# ProPrj___2024-09-22.net
KiCad netlist of a schematic drawn in EasyEDA Pro
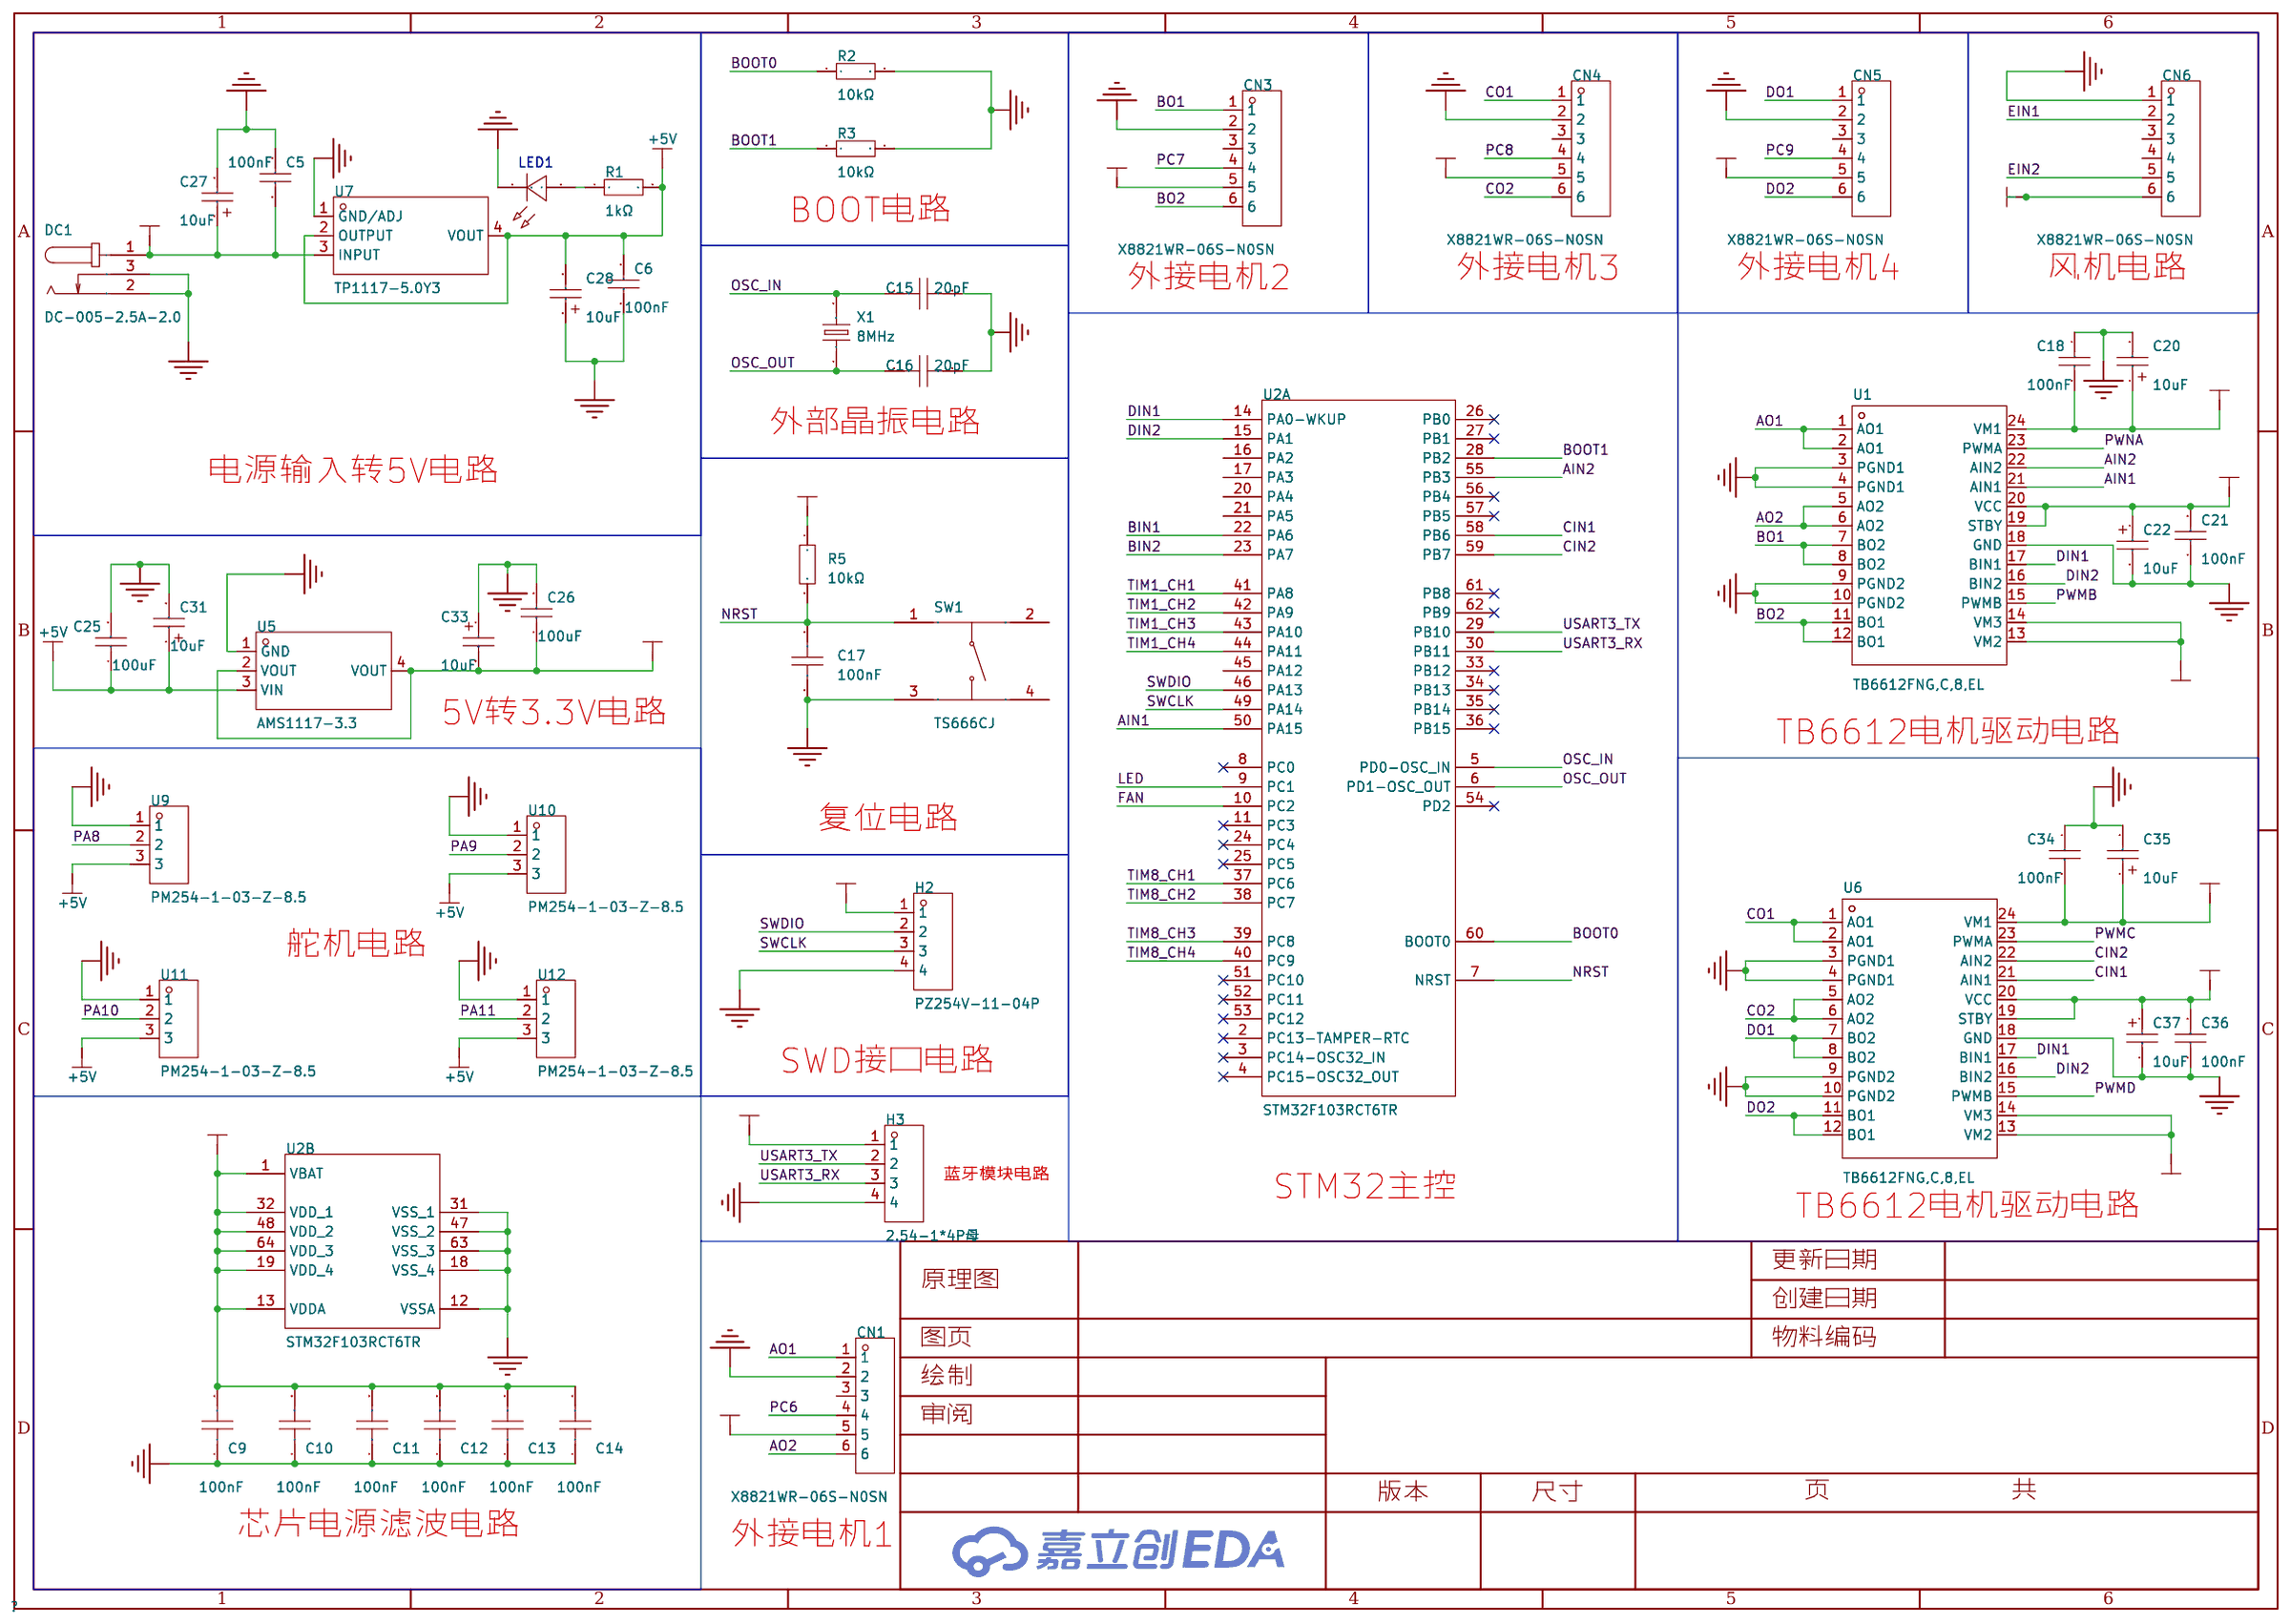
[diagram p0: schematic sheet]

(export (version "E")
  (design (tool "Eeschema 10.0.6"))
  (components
    (comp (ref "C5")
      (value "100nF")
      (footprint "easyedapro:C0805")
      (description "容值:100nF;精度:±10%;额定电压:50V;材质(温度系数):X7R;")
      (fields
        (field (name "Manufacturer Part") "CC0805KRX7R9BB104")
        (field (name "Manufacturer") "YAGEO(国巨)")
      )
      (libsource (lib "easyedapro") (part "CC0805KRX7R9BB104"))
    )
    (comp (ref "C6")
      (value "100nF")
      (footprint "easyedapro:C0805")
      (description "容值:100nF;精度:±10%;额定电压:50V;材质(温度系数):X7R;")
      (fields
        (field (name "Manufacturer Part") "CC0805KRX7R9BB104")
        (field (name "Manufacturer") "YAGEO(国巨)")
      )
      (libsource (lib "easyedapro") (part "CC0805KRX7R9BB104"))
    )
    (comp (ref "C9")
      (value "100nF")
      (footprint "easyedapro:C0603")
      (description "容值:100nF;精度:±10%;额定电压:50V;材质(温度系数):X7R;")
      (fields
        (field (name "Manufacturer Part") "CC0603KRX7R9BB104")
        (field (name "Manufacturer") "YAGEO(国巨)")
      )
      (libsource (lib "easyedapro") (part "CC0603KRX7R9BB104"))
    )
    (comp (ref "C10")
      (value "100nF")
      (footprint "easyedapro:C0603")
      (description "容值:100nF;精度:±10%;额定电压:50V;材质(温度系数):X7R;")
      (fields
        (field (name "Manufacturer Part") "CC0603KRX7R9BB104")
        (field (name "Manufacturer") "YAGEO(国巨)")
      )
      (libsource (lib "easyedapro") (part "CC0603KRX7R9BB104"))
    )
    (comp (ref "C11")
      (value "100nF")
      (footprint "easyedapro:C0603")
      (description "容值:100nF;精度:±10%;额定电压:50V;材质(温度系数):X7R;")
      (fields
        (field (name "Manufacturer Part") "CC0603KRX7R9BB104")
        (field (name "Manufacturer") "YAGEO(国巨)")
      )
      (libsource (lib "easyedapro") (part "CC0603KRX7R9BB104"))
    )
    (comp (ref "C12")
      (value "100nF")
      (footprint "easyedapro:C0603")
      (description "容值:100nF;精度:±10%;额定电压:50V;材质(温度系数):X7R;")
      (fields
        (field (name "Manufacturer Part") "CC0603KRX7R9BB104")
        (field (name "Manufacturer") "YAGEO(国巨)")
      )
      (libsource (lib "easyedapro") (part "CC0603KRX7R9BB104"))
    )
    (comp (ref "C13")
      (value "100nF")
      (footprint "easyedapro:C0603")
      (description "容值:100nF;精度:±10%;额定电压:50V;材质(温度系数):X7R;")
      (fields
        (field (name "Manufacturer Part") "CC0603KRX7R9BB104")
        (field (name "Manufacturer") "YAGEO(国巨)")
      )
      (libsource (lib "easyedapro") (part "CC0603KRX7R9BB104"))
    )
    (comp (ref "C14")
      (value "100nF")
      (footprint "easyedapro:C0603")
      (description "容值:100nF;精度:±10%;额定电压:50V;材质(温度系数):X7R;")
      (fields
        (field (name "Manufacturer Part") "CC0603KRX7R9BB104")
        (field (name "Manufacturer") "YAGEO(国巨)")
      )
      (libsource (lib "easyedapro") (part "CC0603KRX7R9BB104"))
    )
    (comp (ref "C15")
      (value "20pF")
      (footprint "easyedapro:C0805")
      (description "容值:20pF;精度:±5%;额定电压:50V;材质(温度系数):C0G;")
      (fields (field (name "Manufacturer Part") "0805CG200J500NT") (field (name "Manufacturer") "FH(风华)"))
      (libsource (lib "easyedapro") (part "0805CG200J500NT"))
    )
    (comp (ref "C16")
      (value "20pF")
      (footprint "easyedapro:C0805")
      (description "容值:20pF;精度:±5%;额定电压:50V;材质(温度系数):C0G;")
      (fields (field (name "Manufacturer Part") "0805CG200J500NT") (field (name "Manufacturer") "FH(风华)"))
      (libsource (lib "easyedapro") (part "0805CG200J500NT"))
    )
    (comp (ref "C17")
      (value "100nF")
      (footprint "easyedapro:C0603")
      (description "容值:100nF;精度:±10%;额定电压:50V;材质(温度系数):X7R;")
      (fields
        (field (name "Manufacturer Part") "CC0603KRX7R9BB104")
        (field (name "Manufacturer") "YAGEO(国巨)")
      )
      (libsource (lib "easyedapro") (part "CC0603KRX7R9BB104"))
    )
    (comp (ref "C18")
      (value "100nF")
      (footprint "easyedapro:C0805")
      (description "容值:100nF;精度:±10%;额定电压:50V;材质(温度系数):X7R;")
      (fields
        (field (name "Manufacturer Part") "CC0805KRX7R9BB104")
        (field (name "Manufacturer") "YAGEO(国巨)")
      )
      (libsource (lib "easyedapro") (part "CC0805KRX7R9BB104"))
    )
    (comp (ref "C20")
      (value "10uF")
      (footprint "easyedapro:CAP-SMD_L3.2-W1.6-RD-C7171")
      (description "容值:10uF;精度:±10%;额定电压:16V;等效串联电阻:3Ω@100kHz;")
      (fields (field (name "Manufacturer Part") "TAJA106K016RNJ") (field (name "Manufacturer") "Kyocera AVX"))
      (libsource (lib "easyedapro") (part "TAJA106K016RNJ"))
    )
    (comp (ref "C21")
      (value "100nF")
      (footprint "easyedapro:C0805")
      (description "容值:100nF;精度:±10%;额定电压:50V;材质(温度系数):X7R;")
      (fields
        (field (name "Manufacturer Part") "CC0805KRX7R9BB104")
        (field (name "Manufacturer") "YAGEO(国巨)")
      )
      (libsource (lib "easyedapro") (part "CC0805KRX7R9BB104"))
    )
    (comp (ref "C22")
      (value "10uF")
      (footprint "easyedapro:CAP-SMD_L3.2-W1.6-RD-C7171")
      (description "容值:10uF;精度:±10%;额定电压:16V;等效串联电阻:3Ω@100kHz;")
      (fields (field (name "Manufacturer Part") "TAJA106K016RNJ") (field (name "Manufacturer") "Kyocera AVX"))
      (libsource (lib "easyedapro") (part "TAJA106K016RNJ"))
    )
    (comp (ref "C25")
      (value "100uF")
      (footprint "easyedapro:C0805")
      (description "容值:100uF;精度:±20%;额定电压:6.3V;材质(温度系数):X5R;")
      (fields
        (field (name "Manufacturer Part") "GRM21BR60J107ME15L")
        (field (name "Manufacturer") "muRata(村田)")
      )
      (libsource (lib "easyedapro") (part "GRM21BR60J107ME15L"))
    )
    (comp (ref "C26")
      (value "100uF")
      (footprint "easyedapro:C0805")
      (description "容值:100uF;精度:±20%;额定电压:6.3V;材质(温度系数):X5R;")
      (fields
        (field (name "Manufacturer Part") "GRM21BR60J107ME15L")
        (field (name "Manufacturer") "muRata(村田)")
      )
      (libsource (lib "easyedapro") (part "GRM21BR60J107ME15L"))
    )
    (comp (ref "C27")
      (value "10uF")
      (footprint "easyedapro:CAP-SMD_L3.2-W1.6-RD-C7171")
      (description "容值:10uF;精度:±10%;额定电压:16V;等效串联电阻:3Ω@100kHz;")
      (fields (field (name "Manufacturer Part") "TAJA106K016RNJ") (field (name "Manufacturer") "Kyocera AVX"))
      (libsource (lib "easyedapro") (part "TAJA106K016RNJ"))
    )
    (comp (ref "C28")
      (value "10uF")
      (footprint "easyedapro:CAP-SMD_L3.2-W1.6-RD-C7171")
      (description "容值:10uF;精度:±10%;额定电压:16V;等效串联电阻:3Ω@100kHz;")
      (fields (field (name "Manufacturer Part") "TAJA106K016RNJ") (field (name "Manufacturer") "Kyocera AVX"))
      (libsource (lib "easyedapro") (part "TAJA106K016RNJ"))
    )
    (comp (ref "C31")
      (value "10uF")
      (footprint "easyedapro:CAP-SMD_L3.2-W1.6-RD-C7171")
      (description "容值:10uF;精度:±10%;额定电压:16V;等效串联电阻:3Ω@100kHz;")
      (fields (field (name "Manufacturer Part") "TAJA106K016RNJ") (field (name "Manufacturer") "Kyocera AVX"))
      (libsource (lib "easyedapro") (part "TAJA106K016RNJ"))
    )
    (comp (ref "C33")
      (value "10uF")
      (footprint "easyedapro:CAP-SMD_L3.2-W1.6-RD-C7171")
      (description "容值:10uF;精度:±10%;额定电压:16V;等效串联电阻:3Ω@100kHz;")
      (fields (field (name "Manufacturer Part") "TAJA106K016RNJ") (field (name "Manufacturer") "Kyocera AVX"))
      (libsource (lib "easyedapro") (part "TAJA106K016RNJ"))
    )
    (comp (ref "C34")
      (value "100nF")
      (footprint "easyedapro:C0805")
      (description "容值:100nF;精度:±10%;额定电压:50V;材质(温度系数):X7R;")
      (fields
        (field (name "Manufacturer Part") "CC0805KRX7R9BB104")
        (field (name "Manufacturer") "YAGEO(国巨)")
      )
      (libsource (lib "easyedapro") (part "CC0805KRX7R9BB104"))
    )
    (comp (ref "C35")
      (value "10uF")
      (footprint "easyedapro:CAP-SMD_L3.2-W1.6-RD-C7171")
      (description "容值:10uF;精度:±10%;额定电压:16V;等效串联电阻:3Ω@100kHz;")
      (fields (field (name "Manufacturer Part") "TAJA106K016RNJ") (field (name "Manufacturer") "Kyocera AVX"))
      (libsource (lib "easyedapro") (part "TAJA106K016RNJ"))
    )
    (comp (ref "C36")
      (value "100nF")
      (footprint "easyedapro:C0805")
      (description "容值:100nF;精度:±10%;额定电压:50V;材质(温度系数):X7R;")
      (fields
        (field (name "Manufacturer Part") "CC0805KRX7R9BB104")
        (field (name "Manufacturer") "YAGEO(国巨)")
      )
      (libsource (lib "easyedapro") (part "CC0805KRX7R9BB104"))
    )
    (comp (ref "C37")
      (value "10uF")
      (footprint "easyedapro:CAP-SMD_L3.2-W1.6-RD-C7171")
      (description "容值:10uF;精度:±10%;额定电压:16V;等效串联电阻:3Ω@100kHz;")
      (fields (field (name "Manufacturer Part") "TAJA106K016RNJ") (field (name "Manufacturer") "Kyocera AVX"))
      (libsource (lib "easyedapro") (part "TAJA106K016RNJ"))
    )
    (comp (ref "CN1")
      (value "X8821WR-06S-N0SN")
      (footprint "easyedapro:CONN-TH_6P-P2.50_X8821WR-06S-N2SN")
      (description "插针结构:1x6P;间距:2.5mm;安装方式:弯插;参考系列:XH;总PIN数:6P;排数:1;每排PIN数:6;行距:-;额定电流:3A;触头材质:黄铜;触头镀层:锡;工作温度范围:-;")
      (fields (field (name "Manufacturer") "XKB Connection(中国星坤)"))
      (libsource (lib "easyedapro") (part "X8821WR-06S-N0SN"))
    )
    (comp (ref "CN3")
      (value "X8821WR-06S-N0SN")
      (footprint "easyedapro:CONN-TH_6P-P2.50_X8821WR-06S-N2SN")
      (description "插针结构:1x6P;间距:2.5mm;安装方式:弯插;参考系列:XH;总PIN数:6P;排数:1;每排PIN数:6;行距:-;额定电流:3A;触头材质:黄铜;触头镀层:锡;工作温度范围:-;")
      (fields (field (name "Manufacturer") "XKB Connection(中国星坤)"))
      (libsource (lib "easyedapro") (part "X8821WR-06S-N0SN"))
    )
    (comp (ref "CN4")
      (value "X8821WR-06S-N0SN")
      (footprint "easyedapro:CONN-TH_6P-P2.50_X8821WR-06S-N2SN")
      (description "插针结构:1x6P;间距:2.5mm;安装方式:弯插;参考系列:XH;总PIN数:6P;排数:1;每排PIN数:6;行距:-;额定电流:3A;触头材质:黄铜;触头镀层:锡;工作温度范围:-;")
      (fields (field (name "Manufacturer") "XKB Connection(中国星坤)"))
      (libsource (lib "easyedapro") (part "X8821WR-06S-N0SN"))
    )
    (comp (ref "CN5")
      (value "X8821WR-06S-N0SN")
      (footprint "easyedapro:CONN-TH_6P-P2.50_X8821WR-06S-N2SN")
      (description "插针结构:1x6P;间距:2.5mm;安装方式:弯插;参考系列:XH;总PIN数:6P;排数:1;每排PIN数:6;行距:-;额定电流:3A;触头材质:黄铜;触头镀层:锡;工作温度范围:-;")
      (fields (field (name "Manufacturer") "XKB Connection(中国星坤)"))
      (libsource (lib "easyedapro") (part "X8821WR-06S-N0SN"))
    )
    (comp (ref "CN6")
      (value "X8821WR-06S-N0SN")
      (footprint "easyedapro:CONN-TH_6P-P2.50_X8821WR-06S-N2SN")
      (description "插针结构:1x6P;间距:2.5mm;安装方式:弯插;参考系列:XH;总PIN数:6P;排数:1;每排PIN数:6;行距:-;额定电流:3A;触头材质:黄铜;触头镀层:锡;工作温度范围:-;")
      (fields (field (name "Manufacturer") "XKB Connection(中国星坤)"))
      (libsource (lib "easyedapro") (part "X8821WR-06S-N0SN"))
    )
    (comp (ref "DC1")
      (value "DC-005-2.5A-2.0")
      (footprint "easyedapro:CONN-TH_DC-005-2.5A-2.0")
      (fields (field (name "Manufacturer") "XKB Connection(中国星坤)"))
      (libsource (lib "easyedapro") (part "DC-005-2.5A-2.0"))
    )
    (comp (ref "H2")
      (value "PZ254V-11-04P")
      (footprint "easyedapro:HDR-TH_4P-P2.54-V-M")
      (fields (field (name "Manufacturer") "XFCN(兴飞)"))
      (libsource (lib "easyedapro") (part "PZ254V-11-04P_C2691448"))
    )
    (comp (ref "H3")
      (value "2.54-1*4P母")
      (footprint "easyedapro:HDR-TH_4P-P2.54-V-F")
      (fields (field (name "Manufacturer") "BOOMELE(博穆精密)"))
      (libsource (lib "easyedapro") (part "2.54-1*4P母"))
    )
    (comp (ref "LED1")
      (value "~")
      (footprint "easyedapro:LED_0805")
      (libsource (lib "easyedapro") (part "LED_B"))
    )
    (comp (ref "R1")
      (value "1kΩ")
      (footprint "easyedapro:R0805")
      (description "电阻类型:厚膜电阻;阻值:1kΩ;精度:±1%;功率:125mW;最大工作电压:150V;温度系数:±100ppm/°C;")
      (fields
        (field (name "Manufacturer Part") "0805W8F1001T5E")
        (field (name "Manufacturer") "UNI-ROYAL(厚声)")
      )
      (libsource (lib "easyedapro") (part "0805W8F1001T5E"))
    )
    (comp (ref "R2")
      (value "10kΩ")
      (footprint "easyedapro:R0603")
      (description "电阻类型:厚膜电阻;阻值:10kΩ;精度:±1%;功率:100mW;最大工作电压:75V;温度系数:±100ppm/°C;")
      (fields
        (field (name "Manufacturer Part") "0603WAF1002T5E")
        (field (name "Manufacturer") "UNI-ROYAL(厚声)")
      )
      (libsource (lib "easyedapro") (part "0603WAF1002T5E"))
    )
    (comp (ref "R3")
      (value "10kΩ")
      (footprint "easyedapro:R0603")
      (description "电阻类型:厚膜电阻;阻值:10kΩ;精度:±1%;功率:100mW;最大工作电压:75V;温度系数:±100ppm/°C;")
      (fields
        (field (name "Manufacturer Part") "0603WAF1002T5E")
        (field (name "Manufacturer") "UNI-ROYAL(厚声)")
      )
      (libsource (lib "easyedapro") (part "0603WAF1002T5E"))
    )
    (comp (ref "R5")
      (value "10kΩ")
      (footprint "easyedapro:R0603")
      (description "电阻类型:厚膜电阻;阻值:10kΩ;精度:±1%;功率:100mW;最大工作电压:75V;温度系数:±100ppm/°C;")
      (fields
        (field (name "Manufacturer Part") "0603WAF1002T5E")
        (field (name "Manufacturer") "UNI-ROYAL(厚声)")
      )
      (libsource (lib "easyedapro") (part "0603WAF1002T5E"))
    )
    (comp (ref "SW1")
      (value "TS666CJ")
      (footprint "easyedapro:SW-TH_4P-L6.0-W6.0-P4.50-LS6.5")
      (fields (field (name "Manufacturer") "SHOU HAN(首韩)"))
      (libsource (lib "easyedapro") (part "TS666CJ"))
    )
    (comp (ref "U1")
      (value "TB6612FNG,C,8,EL")
      (footprint "easyedapro:SSOP-24_L8.3-W5.6-P0.65-LS7.6-BL")
      (fields (field (name "Manufacturer") "TOSHIBA(东芝)"))
      (libsource (lib "easyedapro") (part "TB6612FNG,C,8,EL"))
    )
    (comp (ref "U2")
      (value "STM32F103RCT6TR")
      (footprint "easyedapro:LQFP-64_L10.0-W10.0-P0.50-LS12.0-BL")
      (description "CPU内核:ARM-M3;程序存储容量:256KB;RAM总容量:48KB;GPIO端口数量:51;工作电压范围:2V~3.6V;CPU最大主频:72MHz;程序存储器类型:FLASH;")
      (fields (field (name "Manufacturer") "ST(意法半导体)"))
      (libsource (lib "easyedapro") (part "STM32F103RCT6TR"))
    )
    (comp (ref "U5")
      (value "AMS1117-3.3")
      (footprint "easyedapro:SOT-223-3_L6.5-W3.4-P2.30-LS7.0-BR")
      (description "输出类型:固定;最大输入电压:-;输出电压:3.3V;最大输出电流:1A;电源纹波抑制比(PSRR):72dB@(120Hz);输出极性:正极;")
      (fields (field (name "Manufacturer") "AMS"))
      (libsource (lib "easyedapro") (part "AMS1117-3.3"))
    )
    (comp (ref "U6")
      (value "TB6612FNG,C,8,EL")
      (footprint "easyedapro:SSOP-24_L8.3-W5.6-P0.65-LS7.6-BL")
      (fields (field (name "Manufacturer") "TOSHIBA(东芝)"))
      (libsource (lib "easyedapro") (part "TB6612FNG,C,8,EL"))
    )
    (comp (ref "U7")
      (value "TP1117-5.0Y3")
      (footprint "easyedapro:SOT-223-3_L6.5-W3.4-P2.30-LS7.0-BR")
      (fields (field (name "Manufacturer") "TECH PUBLIC(台舟)"))
      (libsource (lib "easyedapro") (part "TP1117-5.0Y3"))
    )
    (comp (ref "U9")
      (value "PM254-1-03-Z-8.5")
      (footprint "easyedapro:HDR-TH_3P-P2.54-V-F")
      (fields (field (name "Manufacturer") "HCTL(华灿天禄)"))
      (libsource (lib "easyedapro") (part "PM254-1-03-Z-8.5"))
    )
    (comp (ref "U10")
      (value "PM254-1-03-Z-8.5")
      (footprint "easyedapro:HDR-TH_3P-P2.54-V-F")
      (fields (field (name "Manufacturer") "HCTL(华灿天禄)"))
      (libsource (lib "easyedapro") (part "PM254-1-03-Z-8.5"))
    )
    (comp (ref "U11")
      (value "PM254-1-03-Z-8.5")
      (footprint "easyedapro:HDR-TH_3P-P2.54-V-F")
      (fields (field (name "Manufacturer") "HCTL(华灿天禄)"))
      (libsource (lib "easyedapro") (part "PM254-1-03-Z-8.5"))
    )
    (comp (ref "U12")
      (value "PM254-1-03-Z-8.5")
      (footprint "easyedapro:HDR-TH_3P-P2.54-V-F")
      (fields (field (name "Manufacturer") "HCTL(华灿天禄)"))
      (libsource (lib "easyedapro") (part "PM254-1-03-Z-8.5"))
    )
    (comp (ref "X1")
      (value "8MHz")
      (footprint "easyedapro:HC-49US_L11.5-W4.5-P4.88")
      (description "晶振类型:直插晶振;频率:8MHz;常温频差:±20ppm;外接负载电容:20pF;频率稳定度(全温):±20ppm;")
      (fields
        (field (name "Manufacturer Part") "49S-8.000-20-20-20/A")
        (field (name "Manufacturer") "LIMING(利明)")
      )
      (libsource (lib "easyedapro") (part "49S-8.000-20-20-20/A"))
    )
  )
  (nets
    (net (code "1") (name "+3.3V") (class "Default")
      (node (ref "C10") (pin "2") (pinfunction "2_2") (pintype "unspecified"))
      (node (ref "C11") (pin "2") (pinfunction "2_2") (pintype "unspecified"))
      (node (ref "C12") (pin "2") (pinfunction "2_2") (pintype "unspecified"))
      (node (ref "C13") (pin "2") (pinfunction "2_2") (pintype "unspecified"))
      (node (ref "C14") (pin "2") (pinfunction "2_2") (pintype "unspecified"))
      (node (ref "C21") (pin "2") (pinfunction "2_2") (pintype "input"))
      (node (ref "C22") (pin "1") (pinfunction "1_1") (pintype "input"))
      (node (ref "C26") (pin "1") (pinfunction "1_1") (pintype "input"))
      (node (ref "C33") (pin "2") (pinfunction "2_2") (pintype "input"))
      (node (ref "C36") (pin "2") (pinfunction "2_2") (pintype "input"))
      (node (ref "C37") (pin "1") (pinfunction "1_1") (pintype "input"))
      (node (ref "C9") (pin "2") (pinfunction "2_2") (pintype "unspecified"))
      (node (ref "CN1") (pin "5") (pinfunction "5_5") (pintype "unspecified"))
      (node (ref "CN3") (pin "5") (pinfunction "5_5") (pintype "unspecified"))
      (node (ref "CN4") (pin "5") (pinfunction "5_5") (pintype "unspecified"))
      (node (ref "CN5") (pin "5") (pinfunction "5_5") (pintype "unspecified"))
      (node (ref "H2") (pin "1") (pinfunction "1_1") (pintype "unspecified"))
      (node (ref "H3") (pin "1") (pinfunction "1_1") (pintype "unspecified"))
      (node (ref "R5") (pin "1") (pinfunction "1_1") (pintype "input"))
      (node (ref "U1") (pin "19") (pinfunction "STBY_19") (pintype "unspecified"))
      (node (ref "U1") (pin "20") (pinfunction "VCC_20") (pintype "unspecified"))
      (node (ref "U2") (pin "1") (pinfunction "VBAT_1") (pintype "unspecified"))
      (node (ref "U2") (pin "13") (pinfunction "VDDA_13") (pintype "unspecified"))
      (node (ref "U2") (pin "19") (pinfunction "VDD_4_19") (pintype "unspecified"))
      (node (ref "U2") (pin "32") (pinfunction "VDD_1_32") (pintype "unspecified"))
      (node (ref "U2") (pin "48") (pinfunction "VDD_2_48") (pintype "unspecified"))
      (node (ref "U2") (pin "64") (pinfunction "VDD_3_64") (pintype "unspecified"))
      (node (ref "U5") (pin "2") (pinfunction "VOUT_2") (pintype "unspecified"))
      (node (ref "U5") (pin "4") (pinfunction "VOUT_4") (pintype "unspecified"))
      (node (ref "U6") (pin "19") (pinfunction "STBY_19") (pintype "unspecified"))
      (node (ref "U6") (pin "20") (pinfunction "VCC_20") (pintype "unspecified"))
    )
    (net (code "2") (name "+5V") (class "Default")
      (node (ref "C25") (pin "1") (pinfunction "1_1") (pintype "input"))
      (node (ref "C28") (pin "2") (pinfunction "2_2") (pintype "input"))
      (node (ref "C31") (pin "1") (pinfunction "1_1") (pintype "input"))
      (node (ref "C6") (pin "1") (pinfunction "1_1") (pintype "input"))
      (node (ref "R1") (pin "2") (pinfunction "2_2") (pintype "input"))
      (node (ref "U10") (pin "3") (pinfunction "3_3") (pintype "unspecified"))
      (node (ref "U11") (pin "3") (pinfunction "3_3") (pintype "unspecified"))
      (node (ref "U12") (pin "3") (pinfunction "3_3") (pintype "unspecified"))
      (node (ref "U5") (pin "3") (pinfunction "VIN_3") (pintype "unspecified"))
      (node (ref "U7") (pin "2") (pinfunction "OUTPUT_2") (pintype "unspecified"))
      (node (ref "U7") (pin "4") (pinfunction "VOUT_4") (pintype "unspecified"))
      (node (ref "U9") (pin "3") (pinfunction "3_3") (pintype "unspecified"))
    )
    (net (code "3") (name "+8V") (class "Default")
      (node (ref "C18") (pin "2") (pinfunction "2_2") (pintype "input"))
      (node (ref "C20") (pin "1") (pinfunction "1_1") (pintype "input"))
      (node (ref "C34") (pin "2") (pinfunction "2_2") (pintype "input"))
      (node (ref "C35") (pin "1") (pinfunction "1_1") (pintype "input"))
      (node (ref "U1") (pin "13") (pinfunction "VM2_13") (pintype "unspecified"))
      (node (ref "U1") (pin "14") (pinfunction "VM3_14") (pintype "unspecified"))
      (node (ref "U1") (pin "24") (pinfunction "VM1_24") (pintype "unspecified"))
      (node (ref "U6") (pin "13") (pinfunction "VM2_13") (pintype "unspecified"))
      (node (ref "U6") (pin "14") (pinfunction "VM3_14") (pintype "unspecified"))
      (node (ref "U6") (pin "24") (pinfunction "VM1_24") (pintype "unspecified"))
    )
    (net (code "4") (name "+12V") (class "Default")
      (node (ref "CN6") (pin "6") (pinfunction "6_6") (pintype "unspecified"))
    )
    (net (code "5") (name "/AIN1") (class "Default")
      (node (ref "U1") (pin "21") (pinfunction "AIN1_21") (pintype "unspecified"))
      (node (ref "U2") (pin "50") (pinfunction "PA15_50") (pintype "bidirectional"))
    )
    (net (code "6") (name "/AIN2") (class "Default")
      (node (ref "U1") (pin "22") (pinfunction "AIN2_22") (pintype "unspecified"))
      (node (ref "U2") (pin "55") (pinfunction "PB3_55") (pintype "bidirectional"))
    )
    (net (code "7") (name "/AO1") (class "Default")
      (node (ref "CN1") (pin "1") (pinfunction "1_1") (pintype "unspecified"))
      (node (ref "U1") (pin "1") (pinfunction "AO1_1") (pintype "unspecified"))
      (node (ref "U1") (pin "2") (pinfunction "AO1_2") (pintype "unspecified"))
    )
    (net (code "8") (name "/AO2") (class "Default")
      (node (ref "CN1") (pin "6") (pinfunction "6_6") (pintype "unspecified"))
      (node (ref "U1") (pin "5") (pinfunction "AO2_5") (pintype "unspecified"))
      (node (ref "U1") (pin "6") (pinfunction "AO2_6") (pintype "unspecified"))
    )
    (net (code "9") (name "/BIN1") (class "Default")
      (node (ref "U2") (pin "22") (pinfunction "PA6_22") (pintype "bidirectional"))
    )
    (net (code "10") (name "/BIN2") (class "Default")
      (node (ref "U2") (pin "23") (pinfunction "PA7_23") (pintype "bidirectional"))
    )
    (net (code "11") (name "/BO1") (class "Default")
      (node (ref "CN3") (pin "1") (pinfunction "1_1") (pintype "unspecified"))
      (node (ref "U1") (pin "7") (pinfunction "BO2_7") (pintype "unspecified"))
      (node (ref "U1") (pin "8") (pinfunction "BO2_8") (pintype "unspecified"))
    )
    (net (code "12") (name "/BO2") (class "Default")
      (node (ref "CN3") (pin "6") (pinfunction "6_6") (pintype "unspecified"))
      (node (ref "U1") (pin "11") (pinfunction "BO1_11") (pintype "unspecified"))
      (node (ref "U1") (pin "12") (pinfunction "BO1_12") (pintype "unspecified"))
    )
    (net (code "13") (name "/BOOT0") (class "Default")
      (node (ref "R2") (pin "1") (pinfunction "1_1") (pintype "input"))
      (node (ref "U2") (pin "60") (pinfunction "BOOT0_60") (pintype "unspecified"))
    )
    (net (code "14") (name "/BOOT1") (class "Default")
      (node (ref "R3") (pin "1") (pinfunction "1_1") (pintype "input"))
      (node (ref "U2") (pin "28") (pinfunction "PB2_28") (pintype "bidirectional"))
    )
    (net (code "15") (name "/CIN1") (class "Default")
      (node (ref "U2") (pin "58") (pinfunction "PB6_58") (pintype "bidirectional"))
      (node (ref "U6") (pin "21") (pinfunction "AIN1_21") (pintype "unspecified"))
    )
    (net (code "16") (name "/CIN2") (class "Default")
      (node (ref "U2") (pin "59") (pinfunction "PB7_59") (pintype "bidirectional"))
      (node (ref "U6") (pin "22") (pinfunction "AIN2_22") (pintype "unspecified"))
    )
    (net (code "17") (name "/CO1") (class "Default")
      (node (ref "CN4") (pin "1") (pinfunction "1_1") (pintype "unspecified"))
      (node (ref "U6") (pin "1") (pinfunction "AO1_1") (pintype "unspecified"))
      (node (ref "U6") (pin "2") (pinfunction "AO1_2") (pintype "unspecified"))
    )
    (net (code "18") (name "/CO2") (class "Default")
      (node (ref "CN4") (pin "6") (pinfunction "6_6") (pintype "unspecified"))
      (node (ref "U6") (pin "5") (pinfunction "AO2_5") (pintype "unspecified"))
      (node (ref "U6") (pin "6") (pinfunction "AO2_6") (pintype "unspecified"))
    )
    (net (code "19") (name "/DIN1") (class "Default")
      (node (ref "U1") (pin "17") (pinfunction "BIN1_17") (pintype "unspecified"))
      (node (ref "U2") (pin "14") (pinfunction "PA0-WKUP_14") (pintype "bidirectional"))
      (node (ref "U6") (pin "17") (pinfunction "BIN1_17") (pintype "unspecified"))
    )
    (net (code "20") (name "/DIN2") (class "Default")
      (node (ref "U1") (pin "16") (pinfunction "BIN2_16") (pintype "unspecified"))
      (node (ref "U2") (pin "15") (pinfunction "PA1_15") (pintype "bidirectional"))
      (node (ref "U6") (pin "16") (pinfunction "BIN2_16") (pintype "unspecified"))
    )
    (net (code "21") (name "/DO1") (class "Default")
      (node (ref "CN5") (pin "1") (pinfunction "1_1") (pintype "unspecified"))
      (node (ref "U6") (pin "7") (pinfunction "BO2_7") (pintype "unspecified"))
      (node (ref "U6") (pin "8") (pinfunction "BO2_8") (pintype "unspecified"))
    )
    (net (code "22") (name "/DO2") (class "Default")
      (node (ref "CN5") (pin "6") (pinfunction "6_6") (pintype "unspecified"))
      (node (ref "U6") (pin "11") (pinfunction "BO1_11") (pintype "unspecified"))
      (node (ref "U6") (pin "12") (pinfunction "BO1_12") (pintype "unspecified"))
    )
    (net (code "23") (name "/EIN1") (class "Default")
      (node (ref "CN6") (pin "2") (pinfunction "2_2") (pintype "unspecified"))
    )
    (net (code "24") (name "/EIN2") (class "Default")
      (node (ref "CN6") (pin "5") (pinfunction "5_5") (pintype "unspecified"))
    )
    (net (code "25") (name "/FAN") (class "Default")
      (node (ref "U2") (pin "10") (pinfunction "PC2_10") (pintype "bidirectional"))
    )
    (net (code "26") (name "/LED") (class "Default")
      (node (ref "U2") (pin "9") (pinfunction "PC1_9") (pintype "bidirectional"))
    )
    (net (code "27") (name "/NRST") (class "Default")
      (node (ref "C17") (pin "2") (pinfunction "2_2") (pintype "unspecified"))
      (node (ref "R5") (pin "2") (pinfunction "2_2") (pintype "input"))
      (node (ref "SW1") (pin "1") (pinfunction "A_1") (pintype "input"))
      (node (ref "U2") (pin "7") (pinfunction "NRST_7") (pintype "bidirectional"))
    )
    (net (code "28") (name "/OSC_IN") (class "Default")
      (node (ref "C15") (pin "1") (pinfunction "1_1") (pintype "unspecified"))
      (node (ref "U2") (pin "5") (pinfunction "PD0-OSC_IN_5") (pintype "bidirectional"))
      (node (ref "X1") (pin "2") (pinfunction "2_2") (pintype "input"))
    )
    (net (code "29") (name "/OSC_OUT") (class "Default")
      (node (ref "C16") (pin "1") (pinfunction "1_1") (pintype "unspecified"))
      (node (ref "U2") (pin "6") (pinfunction "PD1-OSC_OUT_6") (pintype "bidirectional"))
      (node (ref "X1") (pin "1") (pinfunction "1_1") (pintype "input"))
    )
    (net (code "30") (name "/PA8") (class "Default")
      (node (ref "U9") (pin "2") (pinfunction "2_2") (pintype "unspecified"))
    )
    (net (code "31") (name "/PA9") (class "Default")
      (node (ref "U10") (pin "2") (pinfunction "2_2") (pintype "unspecified"))
    )
    (net (code "32") (name "/PA10") (class "Default")
      (node (ref "U11") (pin "2") (pinfunction "2_2") (pintype "unspecified"))
    )
    (net (code "33") (name "/PA11") (class "Default")
      (node (ref "U12") (pin "2") (pinfunction "2_2") (pintype "unspecified"))
    )
    (net (code "34") (name "/PC6") (class "Default")
      (node (ref "CN1") (pin "4") (pinfunction "4_4") (pintype "unspecified"))
    )
    (net (code "35") (name "/PC7") (class "Default")
      (node (ref "CN3") (pin "4") (pinfunction "4_4") (pintype "unspecified"))
    )
    (net (code "36") (name "/PC8") (class "Default")
      (node (ref "CN4") (pin "4") (pinfunction "4_4") (pintype "unspecified"))
    )
    (net (code "37") (name "/PC9") (class "Default")
      (node (ref "CN5") (pin "4") (pinfunction "4_4") (pintype "unspecified"))
    )
    (net (code "38") (name "/PWMB") (class "Default")
      (node (ref "U1") (pin "15") (pinfunction "PWMB_15") (pintype "unspecified"))
    )
    (net (code "39") (name "/PWMC") (class "Default")
      (node (ref "U6") (pin "23") (pinfunction "PWMA_23") (pintype "unspecified"))
    )
    (net (code "40") (name "/PWMD") (class "Default")
      (node (ref "U6") (pin "15") (pinfunction "PWMB_15") (pintype "unspecified"))
    )
    (net (code "41") (name "/PWNA") (class "Default")
      (node (ref "U1") (pin "23") (pinfunction "PWMA_23") (pintype "unspecified"))
    )
    (net (code "42") (name "/SWCLK") (class "Default")
      (node (ref "H2") (pin "3") (pinfunction "3_3") (pintype "unspecified"))
      (node (ref "U2") (pin "49") (pinfunction "PA14_49") (pintype "bidirectional"))
    )
    (net (code "43") (name "/SWDIO") (class "Default")
      (node (ref "H2") (pin "2") (pinfunction "2_2") (pintype "unspecified"))
      (node (ref "U2") (pin "46") (pinfunction "PA13_46") (pintype "bidirectional"))
    )
    (net (code "44") (name "/TIM1_CH1") (class "Default")
      (node (ref "U2") (pin "41") (pinfunction "PA8_41") (pintype "bidirectional"))
    )
    (net (code "45") (name "/TIM1_CH2") (class "Default")
      (node (ref "U2") (pin "42") (pinfunction "PA9_42") (pintype "bidirectional"))
    )
    (net (code "46") (name "/TIM1_CH3") (class "Default")
      (node (ref "U2") (pin "43") (pinfunction "PA10_43") (pintype "bidirectional"))
    )
    (net (code "47") (name "/TIM1_CH4") (class "Default")
      (node (ref "U2") (pin "44") (pinfunction "PA11_44") (pintype "bidirectional"))
    )
    (net (code "48") (name "/TIM8_CH1") (class "Default")
      (node (ref "U2") (pin "37") (pinfunction "PC6_37") (pintype "bidirectional"))
    )
    (net (code "49") (name "/TIM8_CH2") (class "Default")
      (node (ref "U2") (pin "38") (pinfunction "PC7_38") (pintype "bidirectional"))
    )
    (net (code "50") (name "/TIM8_CH3") (class "Default")
      (node (ref "U2") (pin "39") (pinfunction "PC8_39") (pintype "bidirectional"))
    )
    (net (code "51") (name "/TIM8_CH4") (class "Default")
      (node (ref "U2") (pin "40") (pinfunction "PC9_40") (pintype "bidirectional"))
    )
    (net (code "52") (name "/USART3_RX") (class "Default")
      (node (ref "H3") (pin "3") (pinfunction "3_3") (pintype "unspecified"))
      (node (ref "U2") (pin "30") (pinfunction "PB11_30") (pintype "bidirectional"))
    )
    (net (code "53") (name "/USART3_TX") (class "Default")
      (node (ref "H3") (pin "2") (pinfunction "2_2") (pintype "unspecified"))
      (node (ref "U2") (pin "29") (pinfunction "PB10_29") (pintype "bidirectional"))
    )
    (net (code "54") (name "8V") (class "Default")
      (node (ref "C27") (pin "1") (pinfunction "1_1") (pintype "input"))
      (node (ref "C5") (pin "2") (pinfunction "2_2") (pintype "input"))
      (node (ref "DC1") (pin "1") (pinfunction "1_1") (pintype "unspecified"))
      (node (ref "U7") (pin "3") (pinfunction "INPUT_3") (pintype "unspecified"))
    )
    (net (code "55") (name "GND") (class "Default")
      (node (ref "C10") (pin "1") (pinfunction "1_1") (pintype "unspecified"))
      (node (ref "C11") (pin "1") (pinfunction "1_1") (pintype "unspecified"))
      (node (ref "C12") (pin "1") (pinfunction "1_1") (pintype "unspecified"))
      (node (ref "C13") (pin "1") (pinfunction "1_1") (pintype "unspecified"))
      (node (ref "C14") (pin "1") (pinfunction "1_1") (pintype "unspecified"))
      (node (ref "C15") (pin "2") (pinfunction "2_2") (pintype "unspecified"))
      (node (ref "C16") (pin "2") (pinfunction "2_2") (pintype "unspecified"))
      (node (ref "C17") (pin "1") (pinfunction "1_1") (pintype "unspecified"))
      (node (ref "C18") (pin "1") (pinfunction "1_1") (pintype "input"))
      (node (ref "C20") (pin "2") (pinfunction "2_2") (pintype "input"))
      (node (ref "C21") (pin "1") (pinfunction "1_1") (pintype "input"))
      (node (ref "C22") (pin "2") (pinfunction "2_2") (pintype "input"))
      (node (ref "C25") (pin "2") (pinfunction "2_2") (pintype "input"))
      (node (ref "C26") (pin "2") (pinfunction "2_2") (pintype "input"))
      (node (ref "C27") (pin "2") (pinfunction "2_2") (pintype "input"))
      (node (ref "C28") (pin "1") (pinfunction "1_1") (pintype "input"))
      (node (ref "C31") (pin "2") (pinfunction "2_2") (pintype "input"))
      (node (ref "C33") (pin "1") (pinfunction "1_1") (pintype "input"))
      (node (ref "C34") (pin "1") (pinfunction "1_1") (pintype "input"))
      (node (ref "C35") (pin "2") (pinfunction "2_2") (pintype "input"))
      (node (ref "C36") (pin "1") (pinfunction "1_1") (pintype "input"))
      (node (ref "C37") (pin "2") (pinfunction "2_2") (pintype "input"))
      (node (ref "C5") (pin "1") (pinfunction "1_1") (pintype "input"))
      (node (ref "C6") (pin "2") (pinfunction "2_2") (pintype "input"))
      (node (ref "C9") (pin "1") (pinfunction "1_1") (pintype "unspecified"))
      (node (ref "CN1") (pin "2") (pinfunction "2_2") (pintype "unspecified"))
      (node (ref "CN3") (pin "2") (pinfunction "2_2") (pintype "unspecified"))
      (node (ref "CN4") (pin "2") (pinfunction "2_2") (pintype "unspecified"))
      (node (ref "CN5") (pin "2") (pinfunction "2_2") (pintype "unspecified"))
      (node (ref "CN6") (pin "1") (pinfunction "1_1") (pintype "unspecified"))
      (node (ref "DC1") (pin "2") (pinfunction "2_2") (pintype "unspecified"))
      (node (ref "DC1") (pin "3") (pinfunction "3_3") (pintype "unspecified"))
      (node (ref "H2") (pin "4") (pinfunction "4_4") (pintype "unspecified"))
      (node (ref "H3") (pin "4") (pinfunction "4_4") (pintype "unspecified"))
      (node (ref "LED1") (pin "1") (pinfunction "C_1") (pintype "input"))
      (node (ref "R2") (pin "2") (pinfunction "2_2") (pintype "input"))
      (node (ref "R3") (pin "2") (pinfunction "2_2") (pintype "input"))
      (node (ref "SW1") (pin "3") (pinfunction "C_3") (pintype "input"))
      (node (ref "U1") (pin "10") (pinfunction "PGND2_10") (pintype "unspecified"))
      (node (ref "U1") (pin "18") (pinfunction "GND_18") (pintype "unspecified"))
      (node (ref "U1") (pin "3") (pinfunction "PGND1_3") (pintype "unspecified"))
      (node (ref "U1") (pin "4") (pinfunction "PGND1_4") (pintype "unspecified"))
      (node (ref "U1") (pin "9") (pinfunction "PGND2_9") (pintype "unspecified"))
      (node (ref "U10") (pin "1") (pinfunction "1_1") (pintype "unspecified"))
      (node (ref "U11") (pin "1") (pinfunction "1_1") (pintype "unspecified"))
      (node (ref "U12") (pin "1") (pinfunction "1_1") (pintype "unspecified"))
      (node (ref "U2") (pin "12") (pinfunction "VSSA_12") (pintype "unspecified"))
      (node (ref "U2") (pin "18") (pinfunction "VSS_4_18") (pintype "unspecified"))
      (node (ref "U2") (pin "31") (pinfunction "VSS_1_31") (pintype "unspecified"))
      (node (ref "U2") (pin "47") (pinfunction "VSS_2_47") (pintype "unspecified"))
      (node (ref "U2") (pin "63") (pinfunction "VSS_3_63") (pintype "unspecified"))
      (node (ref "U5") (pin "1") (pinfunction "GND_1") (pintype "unspecified"))
      (node (ref "U6") (pin "10") (pinfunction "PGND2_10") (pintype "unspecified"))
      (node (ref "U6") (pin "18") (pinfunction "GND_18") (pintype "unspecified"))
      (node (ref "U6") (pin "3") (pinfunction "PGND1_3") (pintype "unspecified"))
      (node (ref "U6") (pin "4") (pinfunction "PGND1_4") (pintype "unspecified"))
      (node (ref "U6") (pin "9") (pinfunction "PGND2_9") (pintype "unspecified"))
      (node (ref "U7") (pin "1") (pinfunction "GND/ADJ_1") (pintype "unspecified"))
      (node (ref "U9") (pin "1") (pinfunction "1_1") (pintype "unspecified"))
    )
    (net (code "56") (name "Net-(LED1-A)") (class "Default")
      (node (ref "LED1") (pin "2") (pinfunction "A_2") (pintype "input"))
      (node (ref "R1") (pin "1") (pinfunction "1_1") (pintype "input"))
    )
    (net (code "57") (name "unconnected-(CN1-Pad3)") (class "Default")
      (node (ref "CN1") (pin "3") (pinfunction "3_3") (pintype "unspecified"))
    )
    (net (code "58") (name "unconnected-(CN3-Pad3)") (class "Default")
      (node (ref "CN3") (pin "3") (pinfunction "3_3") (pintype "unspecified"))
    )
    (net (code "59") (name "unconnected-(CN4-Pad3)") (class "Default")
      (node (ref "CN4") (pin "3") (pinfunction "3_3") (pintype "unspecified"))
    )
    (net (code "60") (name "unconnected-(CN5-Pad3)") (class "Default")
      (node (ref "CN5") (pin "3") (pinfunction "3_3") (pintype "unspecified"))
    )
    (net (code "61") (name "unconnected-(CN6-Pad3)") (class "Default")
      (node (ref "CN6") (pin "3") (pinfunction "3_3") (pintype "unspecified"))
    )
    (net (code "62") (name "unconnected-(CN6-Pad4)") (class "Default")
      (node (ref "CN6") (pin "4") (pinfunction "4_4") (pintype "unspecified"))
    )
    (net (code "63") (name "unconnected-(SW1-B-Pad2)") (class "Default")
      (node (ref "SW1") (pin "2") (pinfunction "B_2") (pintype "input"))
    )
    (net (code "64") (name "unconnected-(SW1-D-Pad4)") (class "Default")
      (node (ref "SW1") (pin "4") (pinfunction "D_4") (pintype "input"))
    )
    (net (code "65") (name "unconnected-(U2A-PA2-Pad16)") (class "Default")
      (node (ref "U2") (pin "16") (pinfunction "PA2_16") (pintype "bidirectional"))
    )
    (net (code "66") (name "unconnected-(U2A-PA3-Pad17)") (class "Default")
      (node (ref "U2") (pin "17") (pinfunction "PA3_17") (pintype "bidirectional"))
    )
    (net (code "67") (name "unconnected-(U2A-PA4-Pad20)") (class "Default")
      (node (ref "U2") (pin "20") (pinfunction "PA4_20") (pintype "bidirectional"))
    )
    (net (code "68") (name "unconnected-(U2A-PA5-Pad21)") (class "Default")
      (node (ref "U2") (pin "21") (pinfunction "PA5_21") (pintype "bidirectional"))
    )
    (net (code "69") (name "unconnected-(U2A-PA12-Pad45)") (class "Default")
      (node (ref "U2") (pin "45") (pinfunction "PA12_45") (pintype "bidirectional"))
    )
    (net (code "70") (name "unconnected-(U2A-PB0-Pad26)") (class "Default")
      (node (ref "U2") (pin "26") (pinfunction "PB0_26") (pintype "bidirectional+no_connect"))
    )
    (net (code "71") (name "unconnected-(U2A-PB1-Pad27)") (class "Default")
      (node (ref "U2") (pin "27") (pinfunction "PB1_27") (pintype "bidirectional+no_connect"))
    )
    (net (code "72") (name "unconnected-(U2A-PB4-Pad56)") (class "Default")
      (node (ref "U2") (pin "56") (pinfunction "PB4_56") (pintype "bidirectional+no_connect"))
    )
    (net (code "73") (name "unconnected-(U2A-PB5-Pad57)") (class "Default")
      (node (ref "U2") (pin "57") (pinfunction "PB5_57") (pintype "bidirectional+no_connect"))
    )
    (net (code "74") (name "unconnected-(U2A-PB8-Pad61)") (class "Default")
      (node (ref "U2") (pin "61") (pinfunction "PB8_61") (pintype "bidirectional+no_connect"))
    )
    (net (code "75") (name "unconnected-(U2A-PB9-Pad62)") (class "Default")
      (node (ref "U2") (pin "62") (pinfunction "PB9_62") (pintype "bidirectional+no_connect"))
    )
    (net (code "76") (name "unconnected-(U2A-PB12-Pad33)") (class "Default")
      (node (ref "U2") (pin "33") (pinfunction "PB12_33") (pintype "bidirectional+no_connect"))
    )
    (net (code "77") (name "unconnected-(U2A-PB13-Pad34)") (class "Default")
      (node (ref "U2") (pin "34") (pinfunction "PB13_34") (pintype "bidirectional+no_connect"))
    )
    (net (code "78") (name "unconnected-(U2A-PB14-Pad35)") (class "Default")
      (node (ref "U2") (pin "35") (pinfunction "PB14_35") (pintype "bidirectional+no_connect"))
    )
    (net (code "79") (name "unconnected-(U2A-PB15-Pad36)") (class "Default")
      (node (ref "U2") (pin "36") (pinfunction "PB15_36") (pintype "bidirectional+no_connect"))
    )
    (net (code "80") (name "unconnected-(U2A-PC0-Pad8)") (class "Default")
      (node (ref "U2") (pin "8") (pinfunction "PC0_8") (pintype "bidirectional+no_connect"))
    )
    (net (code "81") (name "unconnected-(U2A-PC3-Pad11)") (class "Default")
      (node (ref "U2") (pin "11") (pinfunction "PC3_11") (pintype "bidirectional+no_connect"))
    )
    (net (code "82") (name "unconnected-(U2A-PC4-Pad24)") (class "Default")
      (node (ref "U2") (pin "24") (pinfunction "PC4_24") (pintype "bidirectional+no_connect"))
    )
    (net (code "83") (name "unconnected-(U2A-PC5-Pad25)") (class "Default")
      (node (ref "U2") (pin "25") (pinfunction "PC5_25") (pintype "bidirectional+no_connect"))
    )
    (net (code "84") (name "unconnected-(U2A-PC10-Pad51)") (class "Default")
      (node (ref "U2") (pin "51") (pinfunction "PC10_51") (pintype "bidirectional+no_connect"))
    )
    (net (code "85") (name "unconnected-(U2A-PC11-Pad52)") (class "Default")
      (node (ref "U2") (pin "52") (pinfunction "PC11_52") (pintype "bidirectional+no_connect"))
    )
    (net (code "86") (name "unconnected-(U2A-PC12-Pad53)") (class "Default")
      (node (ref "U2") (pin "53") (pinfunction "PC12_53") (pintype "bidirectional+no_connect"))
    )
    (net (code "87") (name "unconnected-(U2A-PC13-TAMPER-RTC-Pad2)") (class "Default")
      (node (ref "U2") (pin "2") (pinfunction "PC13-TAMPER-RTC_2") (pintype "bidirectional+no_connect"))
    )
    (net (code "88") (name "unconnected-(U2A-PC14-OSC32_IN-Pad3)") (class "Default")
      (node (ref "U2") (pin "3") (pinfunction "PC14-OSC32_IN_3") (pintype "bidirectional+no_connect"))
    )
    (net (code "89") (name "unconnected-(U2A-PC15-OSC32_OUT-Pad4)") (class "Default")
      (node (ref "U2") (pin "4") (pinfunction "PC15-OSC32_OUT_4") (pintype "bidirectional+no_connect"))
    )
    (net (code "90") (name "unconnected-(U2A-PD2-Pad54)") (class "Default")
      (node (ref "U2") (pin "54") (pinfunction "PD2_54") (pintype "bidirectional+no_connect"))
    )
  )
)
